# ESPGateway.net
KiCad netlist of a schematic drawn in Altium Designer
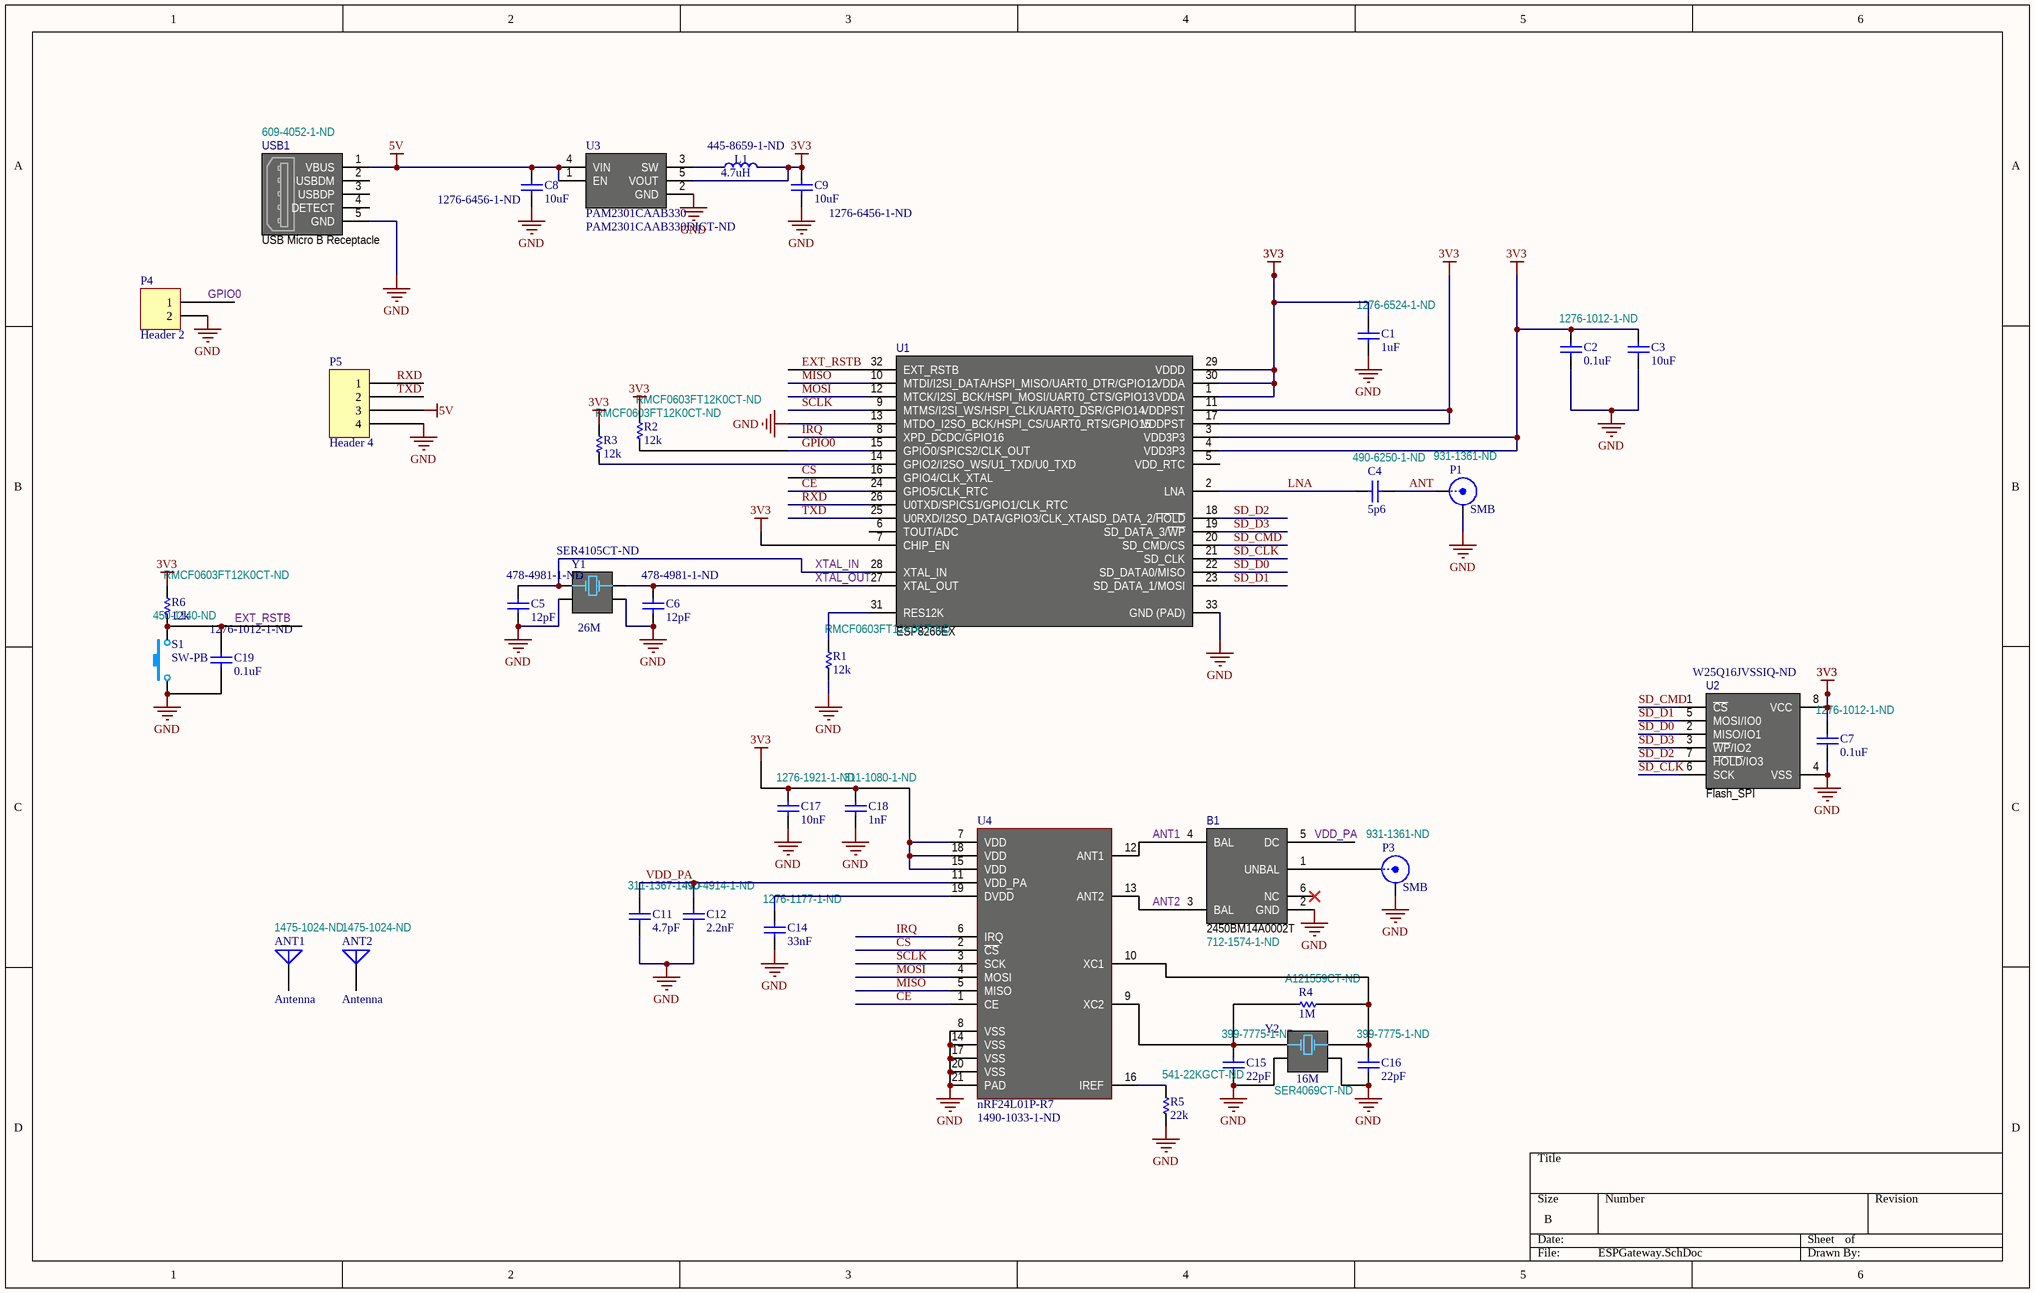
[diagram p0: ESPGateway.SchDoc]

(export (version "E")
  (design (tool "Eeschema 10.0.6"))
  (components
    (comp (ref "ANT1")
      (value "Antenna")
      (footprint "PIN1")
      (description "Generic Antenna")
      (fields
        (field (name "SUPPLIER PART NUMBER 1") "1475-1024-ND")
        (field (name "PUBLISHER") "Altium Limited")
      )
      (libsource (lib "Miscellaneous Devices") (part "Antenna"))
    )
    (comp (ref "ANT2")
      (value "Antenna")
      (footprint "PIN1")
      (description "Generic Antenna")
      (fields
        (field (name "SUPPLIER PART NUMBER 1") "1475-1024-ND")
        (field (name "PUBLISHER") "Altium Limited")
      )
      (libsource (lib "Miscellaneous Devices") (part "Antenna"))
    )
    (comp (ref "B1")
      (value "2450BM14A0002T")
      (footprint "2450BM15A0002E")
      (fields
        (field (name "MANUFACTURER") "Johanson")
        (field (name "SUPPLIER PART NUMBER 1") "712-1574-1-ND")
      )
      (libsource (lib "JTI RF Balun") (part "2450BM14A0002T"))
    )
    (comp (ref "C1")
      (value "1uF")
      (footprint "CAPC1608N")
      (description "Capacitor (Semiconductor SIM Model)")
      (fields
        (field (name "SUPPLIER PART NUMBER 1") "1276-6524-1-ND")
        (field (name "PUBLISHER") "Altium Limited")
      )
      (libsource (lib "Miscellaneous Devices") (part "Cap Semi"))
    )
    (comp (ref "C2")
      (value "0.1uF")
      (footprint "CAPC1608N")
      (description "Capacitor (Semiconductor SIM Model)")
      (fields
        (field (name "SUPPLIER PART NUMBER 2") "1276-1012-1-ND")
        (field (name "PUBLISHER") "Altium Limited")
      )
      (libsource (lib "Miscellaneous Devices") (part "Cap Semi"))
    )
    (comp (ref "C3")
      (value "10uF")
      (footprint "CAPC1608N")
      (description "Capacitor (Semiconductor SIM Model)")
      (fields (field (name "PUBLISHER") "Altium Limited"))
      (libsource (lib "Miscellaneous Devices") (part "Cap Semi"))
    )
    (comp (ref "C4")
      (value "5p6")
      (footprint "CAPC1005N")
      (description "Capacitor (Semiconductor SIM Model)")
      (fields
        (field (name "SUPPLIER PART NUMBER 1") "490-6250-1-ND")
        (field (name "PUBLISHER") "Altium Limited")
      )
      (libsource (lib "Miscellaneous Devices") (part "Cap Semi"))
    )
    (comp (ref "C5")
      (value "12pF")
      (footprint "CAPC1608N")
      (description "Capacitor (Semiconductor SIM Model)")
      (fields
        (field (name "SUPPLIER PART NUMBER 1") "478-4981-1-ND")
        (field (name "PUBLISHER") "Altium Limited")
      )
      (libsource (lib "Miscellaneous Devices") (part "Cap Semi"))
    )
    (comp (ref "C6")
      (value "12pF")
      (footprint "CAPC1608N")
      (description "Capacitor (Semiconductor SIM Model)")
      (fields
        (field (name "SUPPLIER PART NUMBER 1") "478-4981-1-ND")
        (field (name "PUBLISHER") "Altium Limited")
      )
      (libsource (lib "Miscellaneous Devices") (part "Cap Semi"))
    )
    (comp (ref "C7")
      (value "0.1uF")
      (footprint "CAPC1608N")
      (description "Capacitor (Semiconductor SIM Model)")
      (fields
        (field (name "SUPPLIER PART NUMBER 1") "1276-1012-1-ND")
        (field (name "PUBLISHER") "Altium Limited")
      )
      (libsource (lib "Miscellaneous Devices") (part "Cap Semi"))
    )
    (comp (ref "C8")
      (value "10uF")
      (footprint "CAPC2012N")
      (description "Capacitor (Semiconductor SIM Model)")
      (fields
        (field (name "SUPPLIER PART NUMBER 1") "1276-6456-1-ND")
        (field (name "PUBLISHER") "Altium Limited")
      )
      (libsource (lib "Miscellaneous Devices") (part "Cap Semi"))
    )
    (comp (ref "C9")
      (value "10uF")
      (footprint "CAPC2012N")
      (description "Capacitor (Semiconductor SIM Model)")
      (fields
        (field (name "SUPPLIER PART NUMBER 1") "1276-6456-1-ND")
        (field (name "PUBLISHER") "Altium Limited")
      )
      (libsource (lib "Miscellaneous Devices") (part "Cap Semi"))
    )
    (comp (ref "C11")
      (value "4.7pF")
      (footprint "CAPC1005N")
      (description "Capacitor (Semiconductor SIM Model)")
      (fields
        (field (name "SUPPLIER PART NUMBER 1") "311-1367-1-ND")
        (field (name "PUBLISHER") "Altium Limited")
      )
      (libsource (lib "Miscellaneous Devices") (part "Cap Semi"))
    )
    (comp (ref "C12")
      (value "2.2nF")
      (footprint "CAPC1005N")
      (description "Capacitor (Semiconductor SIM Model)")
      (fields
        (field (name "SUPPLIER PART NUMBER 1") "490-4914-1-ND")
        (field (name "PUBLISHER") "Altium Limited")
      )
      (libsource (lib "Miscellaneous Devices") (part "Cap Semi"))
    )
    (comp (ref "C14")
      (value "33nF")
      (footprint "CAPC1005N")
      (description "Capacitor (Semiconductor SIM Model)")
      (fields
        (field (name "SUPPLIER PART NUMBER 2") "1276-1177-1-ND")
        (field (name "PUBLISHER") "Altium Limited")
      )
      (libsource (lib "Miscellaneous Devices") (part "Cap Semi"))
    )
    (comp (ref "C15")
      (value "22pF")
      (footprint "CAPC1005N")
      (description "Capacitor (Semiconductor SIM Model)")
      (fields
        (field (name "SUPPLIER PART NUMBER 1") "399-7775-1-ND")
        (field (name "PUBLISHER") "Altium Limited")
      )
      (libsource (lib "Miscellaneous Devices") (part "Cap Semi"))
    )
    (comp (ref "C16")
      (value "22pF")
      (footprint "CAPC1005N")
      (description "Capacitor (Semiconductor SIM Model)")
      (fields
        (field (name "SUPPLIER PART NUMBER 1") "399-7775-1-ND")
        (field (name "PUBLISHER") "Altium Limited")
      )
      (libsource (lib "Miscellaneous Devices") (part "Cap Semi"))
    )
    (comp (ref "C17")
      (value "10nF")
      (footprint "CAPC1608N")
      (description "Capacitor (Semiconductor SIM Model)")
      (fields
        (field (name "SUPPLIER PART NUMBER 1") "1276-1921-1-ND")
        (field (name "PUBLISHER") "Altium Limited")
      )
      (libsource (lib "Miscellaneous Devices") (part "Cap Semi"))
    )
    (comp (ref "C18")
      (value "1nF")
      (footprint "CAPC1608N")
      (description "Capacitor (Semiconductor SIM Model)")
      (fields
        (field (name "SUPPLIER PART NUMBER 1") "311-1080-1-ND")
        (field (name "PUBLISHER") "Altium Limited")
      )
      (libsource (lib "Miscellaneous Devices") (part "Cap Semi"))
    )
    (comp (ref "C19")
      (value "0.1uF")
      (footprint "CAPC1608N")
      (description "Capacitor (Semiconductor SIM Model)")
      (fields
        (field (name "SUPPLIER PART NUMBER 1") "1276-1012-1-ND")
        (field (name "PUBLISHER") "Altium Limited")
      )
      (libsource (lib "Miscellaneous Devices") (part "Cap Semi"))
    )
    (comp (ref "L1")
      (value "4.7uH")
      (footprint "INDC2012N")
      (description "Inductor")
      (fields
        (field (name "SUPPLIER PART NUMBER 1") "445-8659-1-ND")
        (field (name "PUBLISHER") "Altium Limited")
      )
      (libsource (lib "Miscellaneous Devices") (part "Inductor"))
    )
    (comp (ref "P1")
      (value "SMB")
      (footprint "SMA-J-P-X-RA-TH1")
      (description "SMB Straight Connector")
      (fields
        (field (name "SUPPLIER PART NUMBER 1") "931-1361-ND")
        (field (name "PUBLISHER") "Altium Limited")
      )
      (libsource (lib "Miscellaneous Connectors") (part "SMB"))
    )
    (comp (ref "P3")
      (value "SMB")
      (footprint "SMA-J-P-X-RA-TH1")
      (description "SMB Straight Connector")
      (fields
        (field (name "SUPPLIER PART NUMBER 1") "931-1361-ND")
        (field (name "PUBLISHER") "Altium Limited")
      )
      (libsource (lib "Miscellaneous Connectors") (part "SMB"))
    )
    (comp (ref "P4")
      (value "Header 2")
      (footprint "HDR1X2")
      (description "Header, 2-Pin")
      (fields (field (name "PUBLISHER") "Altium Limited"))
      (libsource (lib "Miscellaneous Connectors") (part "Header 2"))
    )
    (comp (ref "P5")
      (value "Header 4")
      (footprint "HDR1X4")
      (description "Header, 4-Pin")
      (fields (field (name "PUBLISHER") "Altium Limited"))
      (libsource (lib "Miscellaneous Connectors") (part "Header 4"))
    )
    (comp (ref "R1")
      (value "12k")
      (footprint "RESC1608N")
      (description "Semiconductor Resistor")
      (fields
        (field (name "SUPPLIER PART NUMBER 2") "RMCF0603FT12K0CT-ND")
        (field (name "PUBLISHER") "Altium Limited")
      )
      (libsource (lib "Miscellaneous Devices") (part "Res Semi"))
    )
    (comp (ref "R2")
      (value "12k")
      (footprint "RESC1608N")
      (description "Semiconductor Resistor")
      (fields
        (field (name "SUPPLIER PART NUMBER 2") "RMCF0603FT12K0CT-ND")
        (field (name "PUBLISHER") "Altium Limited")
      )
      (libsource (lib "Miscellaneous Devices") (part "Res Semi"))
    )
    (comp (ref "R3")
      (value "12k")
      (footprint "RESC1608N")
      (description "Semiconductor Resistor")
      (fields
        (field (name "SUPPLIER PART NUMBER 2") "RMCF0603FT12K0CT-ND")
        (field (name "PUBLISHER") "Altium Limited")
      )
      (libsource (lib "Miscellaneous Devices") (part "Res Semi"))
    )
    (comp (ref "R4")
      (value "1M")
      (footprint "RESC1005N")
      (description "Semiconductor Resistor")
      (fields
        (field (name "SUPPLIER PART NUMBER 2") "A121559CT-ND")
        (field (name "PUBLISHER") "Altium Limited")
      )
      (libsource (lib "Miscellaneous Devices") (part "Res Semi"))
    )
    (comp (ref "R5")
      (value "22k")
      (footprint "RESC1005N")
      (description "Semiconductor Resistor")
      (fields
        (field (name "SUPPLIER PART NUMBER 2") "541-22KGCT-ND")
        (field (name "PUBLISHER") "Altium Limited")
      )
      (libsource (lib "Miscellaneous Devices") (part "Res Semi"))
    )
    (comp (ref "R6")
      (value "12k")
      (footprint "RESC1608N")
      (description "Semiconductor Resistor")
      (fields
        (field (name "SUPPLIER PART NUMBER 3") "RMCF0603FT12K0CT-ND")
        (field (name "PUBLISHER") "Altium Limited")
      )
      (libsource (lib "Miscellaneous Devices") (part "Res Semi"))
    )
    (comp (ref "S1")
      (value "SW-PB")
      (footprint "FSMSM")
      (description "Switch")
      (fields
        (field (name "SUPPLIER PART NUMBER 1") "450-1140-ND")
        (field (name "PUBLISHER") "Altium Limited")
      )
      (libsource (lib "Miscellaneous Devices") (part "SW-PB"))
    )
    (comp (ref "U1")
      (value "ESP8266EX")
      (footprint "QFN50P500X500-32V2N")
      (libsource (lib "Espressif WiFi Modules") (part "ESP8266EX"))
    )
    (comp (ref "U2")
      (value "Flash_SPI")
      (footprint "SOIC127P1030-8N")
      (fields (field (name "SUPPLIER PART NUMBER 1") "W25Q16JVSSIQ-ND"))
      (libsource (lib "Miscellaneous Devices") (part "Flash_SPI"))
    )
    (comp (ref "U3")
      (value "PAM2301CAAB330")
      (footprint "SOT23-5AN")
      (description "IC REG BCK SYNC 3.3V 0.8A TSOT25")
      (fields
        (field (name "MANUFACTURER") "Diodes")
        (field (name "SUPPLIER PART NUMBER 1") "PAM2301CAAB330DICT-ND")
      )
      (libsource (lib "Diodes Inc Switching Regulator") (part "PAM2301CAAB330"))
    )
    (comp (ref "U4")
      (value "nRF24L01P-R7")
      (footprint "QFN50P400X400-20VN")
      (description "RF Transceiver SNGL-CHP ULTR-LW POW 2.4GHz TRNSCVR")
      (fields
        (field (name "MANUFACTURER") "Nordic Semiconductor")
        (field (name "SUPPLIER PART NUMBER 1") "1490-1033-1-ND")
      )
      (libsource (lib "Nordic nRF24 Series") (part "nRF24L01P-R7"))
    )
    (comp (ref "USB1")
      (value "USB Micro B Receptacle")
      (footprint "10104110-0001LF")
      (fields (field (name "SUPPLIER PART NUMBER 1") "609-4052-1-ND"))
      (libsource (lib "Miscellaneous Connectors") (part "USB Micro B Receptacle"))
    )
    (comp (ref "Y1")
      (value "26M")
      (footprint "XTAL2520-4")
      (description "Crystal Oscillator (4 pin)")
      (fields
        (field (name "SUPPLIER PART NUMBER 1") "SER4105CT-ND")
        (field (name "PUBLISHER") "Altium Limited")
      )
      (libsource (lib "Miscellaneous Devices") (part "XTAL_4SMD"))
    )
    (comp (ref "Y2")
      (value "16M")
      (footprint "XTAL3225-4-N")
      (description "Crystal Oscillator (4 pin)")
      (fields
        (field (name "SUPPLIER PART NUMBER 1") "SER4069CT-ND")
        (field (name "PUBLISHER") "Altium Limited")
      )
      (libsource (lib "Miscellaneous Devices") (part "XTAL_4SMD"))
    )
  )
  (nets
    (net (code "1") (name "/ANT") (class "Default")
      (node (ref "C4") (pin "1") (pinfunction "1_1") (pintype "passive"))
      (node (ref "P1") (pin "1") (pinfunction "X_1") (pintype "passive"))
    )
    (net (code "2") (name "/ANT1") (class "Default")
      (node (ref "B1") (pin "4") (pinfunction "BAL_4") (pintype "passive"))
      (node (ref "U4") (pin "12") (pinfunction "ANT1_12") (pintype "passive"))
    )
    (net (code "3") (name "/ANT2") (class "Default")
      (node (ref "B1") (pin "3") (pinfunction "BAL_3") (pintype "passive"))
      (node (ref "U4") (pin "13") (pinfunction "ANT2_13") (pintype "passive"))
    )
    (net (code "4") (name "/CE") (class "Default")
      (node (ref "U1") (pin "24") (pinfunction "GPIO5/CLK_RTC_24") (pintype "passive"))
      (node (ref "U4") (pin "1") (pinfunction "CE_1") (pintype "passive"))
    )
    (net (code "5") (name "/CS") (class "Default")
      (node (ref "U1") (pin "16") (pinfunction "GPIO4/CLK_XTAL_16") (pintype "passive"))
      (node (ref "U4") (pin "2") (pinfunction "~{CS}_2") (pintype "passive"))
    )
    (net (code "6") (name "/EXT_RSTB") (class "Default")
      (node (ref "C19") (pin "2") (pinfunction "2_2") (pintype "passive"))
      (node (ref "R6") (pin "2") (pinfunction "2_2") (pintype "passive"))
      (node (ref "S1") (pin "2") (pinfunction "2_2") (pintype "passive"))
      (node (ref "U1") (pin "32") (pinfunction "EXT_RSTB_32") (pintype "passive"))
    )
    (net (code "7") (name "/GPIO0") (class "Default")
      (node (ref "P4") (pin "1") (pinfunction "1_1") (pintype "passive"))
      (node (ref "R2") (pin "2") (pinfunction "2_2") (pintype "passive"))
      (node (ref "U1") (pin "15") (pinfunction "GPIO0/SPICS2/CLK_OUT_15") (pintype "passive"))
    )
    (net (code "8") (name "/IRQ") (class "Default")
      (node (ref "U1") (pin "8") (pinfunction "XPD_DCDC/GPIO16_8") (pintype "passive"))
      (node (ref "U4") (pin "6") (pinfunction "IRQ_6") (pintype "passive"))
    )
    (net (code "9") (name "/LNA") (class "Default")
      (node (ref "C4") (pin "2") (pinfunction "2_2") (pintype "passive"))
      (node (ref "U1") (pin "2") (pinfunction "LNA_2") (pintype "passive"))
    )
    (net (code "10") (name "/MISO") (class "Default")
      (node (ref "U1") (pin "10") (pinfunction "MTDI/I2SI_DATA/HSPI_MISO/UART0_DTR/GPIO12_10") (pintype "passive"))
      (node (ref "U4") (pin "5") (pinfunction "MISO_5") (pintype "passive"))
    )
    (net (code "11") (name "/MOSI") (class "Default")
      (node (ref "U1") (pin "12") (pinfunction "MTCK/I2SI_BCK/HSPI_MOSI/UART0_CTS/GPIO13_12") (pintype "passive"))
      (node (ref "U4") (pin "4") (pinfunction "MOSI_4") (pintype "passive"))
    )
    (net (code "12") (name "/RXD") (class "Default")
      (node (ref "P5") (pin "1") (pinfunction "1_1") (pintype "passive"))
      (node (ref "U1") (pin "26") (pinfunction "U0TXD/SPICS1/GPIO1/CLK_RTC_26") (pintype "passive"))
    )
    (net (code "13") (name "/SCLK") (class "Default")
      (node (ref "U1") (pin "9") (pinfunction "MTMS/I2SI_WS/HSPI_CLK/UART0_DSR/GPIO14_9") (pintype "passive"))
      (node (ref "U4") (pin "3") (pinfunction "SCK_3") (pintype "passive"))
    )
    (net (code "14") (name "/SD_CLK") (class "Default")
      (node (ref "U1") (pin "21") (pinfunction "SD_CLK_21") (pintype "passive"))
      (node (ref "U2") (pin "6") (pinfunction "SCK_6") (pintype "passive"))
    )
    (net (code "15") (name "/SD_CMD") (class "Default")
      (node (ref "U1") (pin "20") (pinfunction "SD_CMD/CS_20") (pintype "passive"))
      (node (ref "U2") (pin "1") (pinfunction "~{CS}_1") (pintype "passive"))
    )
    (net (code "16") (name "/SD_D0") (class "Default")
      (node (ref "U1") (pin "22") (pinfunction "SD_DATA0/MISO_22") (pintype "passive"))
      (node (ref "U2") (pin "2") (pinfunction "MISO/IO1_2") (pintype "passive"))
    )
    (net (code "17") (name "/SD_D1") (class "Default")
      (node (ref "U1") (pin "23") (pinfunction "SD_DATA_1/MOSI_23") (pintype "passive"))
      (node (ref "U2") (pin "5") (pinfunction "MOSI/IO0_5") (pintype "passive"))
    )
    (net (code "18") (name "/SD_D2") (class "Default")
      (node (ref "U1") (pin "18") (pinfunction "SD_DATA_2/~{HOLD}_18") (pintype "passive"))
      (node (ref "U2") (pin "7") (pinfunction "~{HOLD}/IO3_7") (pintype "passive"))
    )
    (net (code "19") (name "/SD_D3") (class "Default")
      (node (ref "U1") (pin "19") (pinfunction "SD_DATA_3/~{WP}_19") (pintype "passive"))
      (node (ref "U2") (pin "3") (pinfunction "~{WP}/IO2_3") (pintype "passive"))
    )
    (net (code "20") (name "/TXD") (class "Default")
      (node (ref "P5") (pin "2") (pinfunction "2_2") (pintype "passive"))
      (node (ref "U1") (pin "25") (pinfunction "U0RXD/I2SO_DATA/GPIO3/CLK_XTAL_25") (pintype "passive"))
    )
    (net (code "21") (name "/VDD_PA") (class "Default")
      (node (ref "B1") (pin "5") (pinfunction "DC_5") (pintype "passive"))
      (node (ref "C11") (pin "2") (pinfunction "2_2") (pintype "passive"))
      (node (ref "C12") (pin "2") (pinfunction "2_2") (pintype "passive"))
      (node (ref "U4") (pin "11") (pinfunction "VDD_PA_11") (pintype "passive"))
    )
    (net (code "22") (name "/XTAL_IN") (class "Default")
      (node (ref "C5") (pin "2") (pinfunction "2_2") (pintype "passive"))
      (node (ref "U1") (pin "28") (pinfunction "XTAL_IN_28") (pintype "passive"))
      (node (ref "Y1") (pin "1") (pinfunction "OSC1_1") (pintype "passive"))
    )
    (net (code "23") (name "/XTAL_OUT") (class "Default")
      (node (ref "C6") (pin "2") (pinfunction "2_2") (pintype "passive"))
      (node (ref "U1") (pin "27") (pinfunction "XTAL_OUT_27") (pintype "passive"))
      (node (ref "Y1") (pin "3") (pinfunction "OSC2_3") (pintype "passive"))
    )
    (net (code "24") (name "3V3") (class "Default")
      (node (ref "C1") (pin "2") (pinfunction "2_2") (pintype "passive"))
      (node (ref "C17") (pin "2") (pinfunction "2_2") (pintype "passive"))
      (node (ref "C18") (pin "2") (pinfunction "2_2") (pintype "passive"))
      (node (ref "C2") (pin "2") (pinfunction "2_2") (pintype "passive"))
      (node (ref "C3") (pin "2") (pinfunction "2_2") (pintype "passive"))
      (node (ref "C7") (pin "2") (pinfunction "2_2") (pintype "passive"))
      (node (ref "C9") (pin "2") (pinfunction "2_2") (pintype "passive"))
      (node (ref "L1") (pin "2") (pinfunction "2_2") (pintype "passive"))
      (node (ref "R2") (pin "1") (pinfunction "1_1") (pintype "passive"))
      (node (ref "R3") (pin "1") (pinfunction "1_1") (pintype "passive"))
      (node (ref "R6") (pin "1") (pinfunction "1_1") (pintype "passive"))
      (node (ref "U1") (pin "1") (pinfunction "VDDA_1") (pintype "passive"))
      (node (ref "U1") (pin "11") (pinfunction "VDDPST_11") (pintype "passive"))
      (node (ref "U1") (pin "17") (pinfunction "VDDPST_17") (pintype "passive"))
      (node (ref "U1") (pin "29") (pinfunction "VDDD_29") (pintype "passive"))
      (node (ref "U1") (pin "3") (pinfunction "VDD3P3_3") (pintype "passive"))
      (node (ref "U1") (pin "30") (pinfunction "VDDA_30") (pintype "passive"))
      (node (ref "U1") (pin "4") (pinfunction "VDD3P3_4") (pintype "passive"))
      (node (ref "U1") (pin "7") (pinfunction "CHIP_EN_7") (pintype "passive"))
      (node (ref "U2") (pin "8") (pinfunction "VCC_8") (pintype "passive"))
      (node (ref "U3") (pin "5") (pinfunction "VOUT_5") (pintype "passive"))
      (node (ref "U4") (pin "15") (pinfunction "VDD_15") (pintype "passive"))
      (node (ref "U4") (pin "18") (pinfunction "VDD_18") (pintype "passive"))
      (node (ref "U4") (pin "7") (pinfunction "VDD_7") (pintype "passive"))
    )
    (net (code "25") (name "5V") (class "Default")
      (node (ref "C8") (pin "2") (pinfunction "2_2") (pintype "passive"))
      (node (ref "P5") (pin "3") (pinfunction "3_3") (pintype "passive"))
      (node (ref "U3") (pin "1") (pinfunction "EN_1") (pintype "passive"))
      (node (ref "U3") (pin "4") (pinfunction "VIN_4") (pintype "passive"))
      (node (ref "USB1") (pin "1") (pinfunction "VBUS_1") (pintype "power_in"))
    )
    (net (code "26") (name "GND") (class "Default")
      (node (ref "B1") (pin "2") (pinfunction "GND_2") (pintype "passive"))
      (node (ref "C1") (pin "1") (pinfunction "1_1") (pintype "passive"))
      (node (ref "C11") (pin "1") (pinfunction "1_1") (pintype "passive"))
      (node (ref "C12") (pin "1") (pinfunction "1_1") (pintype "passive"))
      (node (ref "C14") (pin "1") (pinfunction "1_1") (pintype "passive"))
      (node (ref "C15") (pin "1") (pinfunction "1_1") (pintype "passive"))
      (node (ref "C16") (pin "1") (pinfunction "1_1") (pintype "passive"))
      (node (ref "C17") (pin "1") (pinfunction "1_1") (pintype "passive"))
      (node (ref "C18") (pin "1") (pinfunction "1_1") (pintype "passive"))
      (node (ref "C19") (pin "1") (pinfunction "1_1") (pintype "passive"))
      (node (ref "C2") (pin "1") (pinfunction "1_1") (pintype "passive"))
      (node (ref "C3") (pin "1") (pinfunction "1_1") (pintype "passive"))
      (node (ref "C5") (pin "1") (pinfunction "1_1") (pintype "passive"))
      (node (ref "C6") (pin "1") (pinfunction "1_1") (pintype "passive"))
      (node (ref "C7") (pin "1") (pinfunction "1_1") (pintype "passive"))
      (node (ref "C8") (pin "1") (pinfunction "1_1") (pintype "passive"))
      (node (ref "C9") (pin "1") (pinfunction "1_1") (pintype "passive"))
      (node (ref "P1") (pin "2") (pinfunction "Y_2") (pintype "passive"))
      (node (ref "P3") (pin "2") (pinfunction "Y_2") (pintype "passive"))
      (node (ref "P4") (pin "2") (pinfunction "2_2") (pintype "passive"))
      (node (ref "P5") (pin "4") (pinfunction "4_4") (pintype "passive"))
      (node (ref "R1") (pin "1") (pinfunction "1_1") (pintype "passive"))
      (node (ref "R5") (pin "1") (pinfunction "1_1") (pintype "passive"))
      (node (ref "S1") (pin "1") (pinfunction "1_1") (pintype "passive"))
      (node (ref "U1") (pin "13") (pinfunction "MTDO_I2SO_BCK/HSPI_CS/UART0_RTS/GPIO15_13") (pintype "passive"))
      (node (ref "U1") (pin "33") (pinfunction "GND_(PAD)_33") (pintype "passive"))
      (node (ref "U2") (pin "4") (pinfunction "VSS_4") (pintype "passive"))
      (node (ref "U3") (pin "2") (pinfunction "GND_2") (pintype "passive"))
      (node (ref "U4") (pin "14") (pinfunction "VSS_14") (pintype "passive"))
      (node (ref "U4") (pin "17") (pinfunction "VSS_17") (pintype "passive"))
      (node (ref "U4") (pin "20") (pinfunction "VSS_20") (pintype "passive"))
      (node (ref "U4") (pin "21") (pinfunction "PAD_21") (pintype "power_in"))
      (node (ref "U4") (pin "8") (pinfunction "VSS_8") (pintype "passive"))
      (node (ref "USB1") (pin "5") (pinfunction "GND_5") (pintype "power_in"))
      (node (ref "Y1") (pin "2") (pinfunction "2_2") (pintype "power_in"))
      (node (ref "Y1") (pin "4") (pinfunction "4_4") (pintype "power_in"))
      (node (ref "Y2") (pin "2") (pinfunction "2_2") (pintype "power_in"))
      (node (ref "Y2") (pin "4") (pinfunction "4_4") (pintype "power_in"))
    )
    (net (code "27") (name "Net-(B1-UNBAL)") (class "Default")
      (node (ref "B1") (pin "1") (pinfunction "UNBAL_1") (pintype "passive"))
      (node (ref "P3") (pin "1") (pinfunction "X_1") (pintype "passive"))
    )
    (net (code "28") (name "Net-(U1-GPIO2{slash}I2SO_WS{slash}U1_TXD{slash}U0_TXD)") (class "Default")
      (node (ref "R3") (pin "2") (pinfunction "2_2") (pintype "passive"))
      (node (ref "U1") (pin "14") (pinfunction "GPIO2/I2SO_WS/U1_TXD/U0_TXD_14") (pintype "passive"))
    )
    (net (code "29") (name "Net-(U1-RES12K)") (class "Default")
      (node (ref "R1") (pin "2") (pinfunction "2_2") (pintype "passive"))
      (node (ref "U1") (pin "31") (pinfunction "RES12K_31") (pintype "passive"))
    )
    (net (code "30") (name "Net-(U3-SW)") (class "Default")
      (node (ref "L1") (pin "1") (pinfunction "1_1") (pintype "passive"))
      (node (ref "U3") (pin "3") (pinfunction "SW_3") (pintype "passive"))
    )
    (net (code "31") (name "Net-(U4-DVDD)") (class "Default")
      (node (ref "C14") (pin "2") (pinfunction "2_2") (pintype "passive"))
      (node (ref "U4") (pin "19") (pinfunction "DVDD_19") (pintype "passive"))
    )
    (net (code "32") (name "Net-(U4-IREF)") (class "Default")
      (node (ref "R5") (pin "2") (pinfunction "2_2") (pintype "passive"))
      (node (ref "U4") (pin "16") (pinfunction "IREF_16") (pintype "passive"))
    )
    (net (code "33") (name "Net-(U4-XC1)") (class "Default")
      (node (ref "C16") (pin "2") (pinfunction "2_2") (pintype "passive"))
      (node (ref "R4") (pin "1") (pinfunction "1_1") (pintype "passive"))
      (node (ref "U4") (pin "10") (pinfunction "XC1_10") (pintype "passive"))
      (node (ref "Y2") (pin "3") (pinfunction "OSC2_3") (pintype "passive"))
    )
    (net (code "34") (name "Net-(U4-XC2)") (class "Default")
      (node (ref "C15") (pin "2") (pinfunction "2_2") (pintype "passive"))
      (node (ref "R4") (pin "2") (pinfunction "2_2") (pintype "passive"))
      (node (ref "U4") (pin "9") (pinfunction "XC2_9") (pintype "passive"))
      (node (ref "Y2") (pin "1") (pinfunction "OSC1_1") (pintype "passive"))
    )
    (net (code "35") (name "unconnected-(ANT1-A-Pad1)") (class "Default")
      (node (ref "ANT1") (pin "1") (pinfunction "A_1") (pintype "passive"))
    )
    (net (code "36") (name "unconnected-(ANT2-A-Pad1)") (class "Default")
      (node (ref "ANT2") (pin "1") (pinfunction "A_1") (pintype "passive"))
    )
    (net (code "37") (name "unconnected-(B1-NC-Pad6)") (class "Default")
      (node (ref "B1") (pin "6") (pinfunction "NC_6") (pintype "passive+no_connect"))
    )
    (net (code "38") (name "unconnected-(U1-TOUT{slash}ADC-Pad6)") (class "Default")
      (node (ref "U1") (pin "6") (pinfunction "TOUT/ADC_6") (pintype "passive"))
    )
    (net (code "39") (name "unconnected-(U1-VDD_RTC-Pad5)") (class "Default")
      (node (ref "U1") (pin "5") (pinfunction "VDD_RTC_5") (pintype "passive"))
    )
    (net (code "40") (name "unconnected-(USB1-DETECT-Pad4)") (class "Default")
      (node (ref "USB1") (pin "4") (pinfunction "DETECT_4") (pintype "power_in"))
    )
    (net (code "41") (name "unconnected-(USB1-USBDM-Pad2)") (class "Default")
      (node (ref "USB1") (pin "2") (pinfunction "USBDM_2") (pintype "power_in"))
    )
    (net (code "42") (name "unconnected-(USB1-USBDP-Pad3)") (class "Default")
      (node (ref "USB1") (pin "3") (pinfunction "USBDP_3") (pintype "power_in"))
    )
  )
)
